# Armament_HUD_Control_Panel.net
KiCad netlist of a schematic drawn in EAGLE
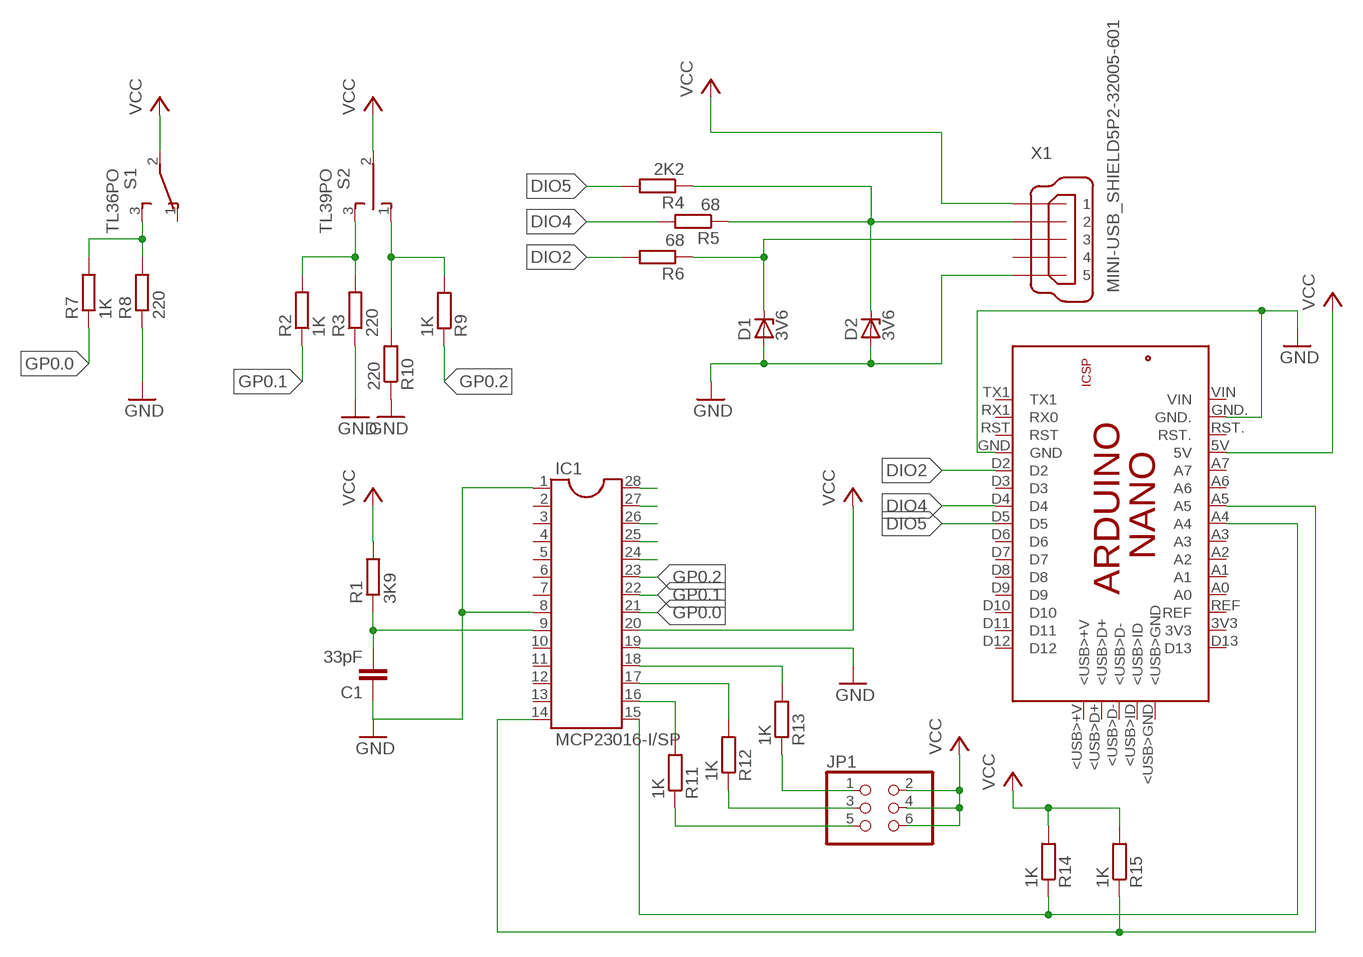
[diagram p0: schematic, sheet 1]

(export (version "E")
  (design (tool "Eeschema 10.0.6"))
  (components
    (comp (ref "C1")
      (value "33pF")
      (footprint "eagle-import:C050-030X075")
      (libsource (lib "eagle-import") (part "C-EU050-030X075"))
    )
    (comp (ref "D1")
      (value "3V6")
      (footprint "eagle-import:DO35Z10")
      (libsource (lib "eagle-import") (part "ZPD"))
    )
    (comp (ref "D2")
      (value "3V6")
      (footprint "eagle-import:DO35Z10")
      (libsource (lib "eagle-import") (part "ZPD"))
    )
    (comp (ref "IC1")
      (value "MCP23016-I/SP")
      (footprint "eagle-import:DIL28-3")
      (libsource (lib "eagle-import") (part "DIL28-3"))
    )
    (comp (ref "JP1")
      (value "PINHD-2X3")
      (footprint "eagle-import:2X03")
      (libsource (lib "eagle-import") (part "PINHD-2X3"))
    )
    (comp (ref "PCB1")
      (value "ARDUINO_NANO")
      (footprint "eagle-import:ARDUINO_NANO")
      (libsource (lib "eagle-import") (part "ARDUINO_NANO"))
    )
    (comp (ref "R1")
      (value "3K9")
      (footprint "eagle-import:0204_7")
      (libsource (lib "eagle-import") (part "R-EU_0204/7"))
    )
    (comp (ref "R2")
      (value "1K")
      (footprint "eagle-import:0204_7")
      (libsource (lib "eagle-import") (part "R-EU_0204/7"))
    )
    (comp (ref "R3")
      (value "220")
      (footprint "eagle-import:0204_7")
      (libsource (lib "eagle-import") (part "R-EU_0204/7"))
    )
    (comp (ref "R4")
      (value "2K2")
      (footprint "eagle-import:0204_7")
      (libsource (lib "eagle-import") (part "R-EU_0204/7"))
    )
    (comp (ref "R5")
      (value "68")
      (footprint "eagle-import:0204_7")
      (libsource (lib "eagle-import") (part "R-EU_0204/7"))
    )
    (comp (ref "R6")
      (value "68")
      (footprint "eagle-import:0204_7")
      (libsource (lib "eagle-import") (part "R-EU_0204/7"))
    )
    (comp (ref "R7")
      (value "1K")
      (footprint "eagle-import:0204_7")
      (libsource (lib "eagle-import") (part "R-EU_0204/7"))
    )
    (comp (ref "R8")
      (value "220")
      (footprint "eagle-import:0204_7")
      (libsource (lib "eagle-import") (part "R-EU_0204/7"))
    )
    (comp (ref "R9")
      (value "1K")
      (footprint "eagle-import:0204_7")
      (libsource (lib "eagle-import") (part "R-EU_0204/7"))
    )
    (comp (ref "R10")
      (value "220")
      (footprint "eagle-import:0204_7")
      (libsource (lib "eagle-import") (part "R-EU_0204/7"))
    )
    (comp (ref "R11")
      (value "1K")
      (footprint "eagle-import:0204_7")
      (libsource (lib "eagle-import") (part "R-EU_0204/7"))
    )
    (comp (ref "R12")
      (value "1K")
      (footprint "eagle-import:0204_7")
      (libsource (lib "eagle-import") (part "R-EU_0204/7"))
    )
    (comp (ref "R13")
      (value "1K")
      (footprint "eagle-import:0204_7")
      (libsource (lib "eagle-import") (part "R-EU_0204/7"))
    )
    (comp (ref "R14")
      (value "1K")
      (footprint "eagle-import:0204_7")
      (libsource (lib "eagle-import") (part "R-EU_0204/7"))
    )
    (comp (ref "R15")
      (value "1K")
      (footprint "eagle-import:0204_7")
      (libsource (lib "eagle-import") (part "R-EU_0204/7"))
    )
    (comp (ref "S1")
      (value "TL36PO")
      (footprint "eagle-import:TL3XPO")
      (libsource (lib "eagle-import") (part "TL36PO"))
    )
    (comp (ref "S2")
      (value "TL39PO")
      (footprint "eagle-import:TL3XPO")
      (libsource (lib "eagle-import") (part "TL39PO"))
    )
    (comp (ref "X1")
      (value "MINI-USB_SHIELD5P2-32005-601")
      (footprint "eagle-import:32005-601")
      (libsource (lib "eagle-import") (part "MINI-USB_SHIELD5P2-32005-601"))
    )
  )
  (nets
    (net (code "1") (name "DIO2") (class "Default")
      (node (ref "PCB1") (pin "D2") (pinfunction "D2_D2") (pintype "bidirectional"))
      (node (ref "R6") (pin "2") (pinfunction "2_2") (pintype "passive"))
    )
    (net (code "2") (name "DIO4") (class "Default")
      (node (ref "PCB1") (pin "D4") (pinfunction "D4_D4") (pintype "bidirectional"))
      (node (ref "R5") (pin "2") (pinfunction "2_2") (pintype "passive"))
    )
    (net (code "3") (name "DIO5") (class "Default")
      (node (ref "PCB1") (pin "D5") (pinfunction "D5_D5") (pintype "bidirectional"))
      (node (ref "R4") (pin "2") (pinfunction "2_2") (pintype "passive"))
    )
    (net (code "4") (name "GND") (class "Default")
      (node (ref "C1") (pin "1") (pinfunction "1_1") (pintype "passive"))
      (node (ref "D1") (pin "A") (pinfunction "A_A") (pintype "passive"))
      (node (ref "D2") (pin "A") (pinfunction "A_A") (pintype "passive"))
      (node (ref "IC1") (pin "1") (pinfunction "1_1") (pintype "passive"))
      (node (ref "IC1") (pin "19") (pinfunction "19_19") (pintype "passive"))
      (node (ref "IC1") (pin "8") (pinfunction "8_8") (pintype "passive"))
      (node (ref "PCB1") (pin "GND") (pinfunction "GND_GND") (pintype "bidirectional"))
      (node (ref "PCB1") (pin "GND.") (pinfunction "GND._GND.") (pintype "bidirectional"))
      (node (ref "R10") (pin "1") (pinfunction "1_1") (pintype "passive"))
      (node (ref "R3") (pin "1") (pinfunction "1_1") (pintype "passive"))
      (node (ref "R8") (pin "1") (pinfunction "1_1") (pintype "passive"))
      (node (ref "X1") (pin "5") (pinfunction "5_5") (pintype "passive"))
    )
    (net (code "5") (name "GP0.0") (class "Default")
      (node (ref "IC1") (pin "21") (pinfunction "21_21") (pintype "passive"))
      (node (ref "R7") (pin "1") (pinfunction "1_1") (pintype "passive"))
    )
    (net (code "6") (name "GP0.1") (class "Default")
      (node (ref "IC1") (pin "22") (pinfunction "22_22") (pintype "passive"))
      (node (ref "R2") (pin "1") (pinfunction "1_1") (pintype "passive"))
    )
    (net (code "7") (name "GP0.2") (class "Default")
      (node (ref "IC1") (pin "23") (pinfunction "23_23") (pintype "passive"))
      (node (ref "R9") (pin "1") (pinfunction "1_1") (pintype "passive"))
    )
    (net (code "8") (name "Net-(C1-Pad2)") (class "Default")
      (node (ref "C1") (pin "2") (pinfunction "2_2") (pintype "passive"))
      (node (ref "IC1") (pin "9") (pinfunction "9_9") (pintype "passive"))
      (node (ref "R1") (pin "1") (pinfunction "1_1") (pintype "passive"))
    )
    (net (code "9") (name "Net-(D1-PadC)") (class "Default")
      (node (ref "D1") (pin "C") (pinfunction "C_C") (pintype "passive"))
      (node (ref "R6") (pin "1") (pinfunction "1_1") (pintype "passive"))
      (node (ref "X1") (pin "3") (pinfunction "3_3") (pintype "passive"))
    )
    (net (code "10") (name "Net-(D2-PadC)") (class "Default")
      (node (ref "D2") (pin "C") (pinfunction "C_C") (pintype "passive"))
      (node (ref "R4") (pin "1") (pinfunction "1_1") (pintype "passive"))
      (node (ref "R5") (pin "1") (pinfunction "1_1") (pintype "passive"))
      (node (ref "X1") (pin "2") (pinfunction "2_2") (pintype "passive"))
    )
    (net (code "11") (name "Net-(IC1-Pad14)") (class "Default")
      (node (ref "IC1") (pin "14") (pinfunction "14_14") (pintype "passive"))
      (node (ref "PCB1") (pin "A5") (pinfunction "A5_A5") (pintype "bidirectional"))
      (node (ref "R15") (pin "1") (pinfunction "1_1") (pintype "passive"))
    )
    (net (code "12") (name "Net-(IC1-Pad15)") (class "Default")
      (node (ref "IC1") (pin "15") (pinfunction "15_15") (pintype "passive"))
      (node (ref "PCB1") (pin "A4") (pinfunction "A4_A4") (pintype "bidirectional"))
      (node (ref "R14") (pin "1") (pinfunction "1_1") (pintype "passive"))
    )
    (net (code "13") (name "Net-(IC1-Pad16)") (class "Default")
      (node (ref "IC1") (pin "16") (pinfunction "16_16") (pintype "passive"))
      (node (ref "R11") (pin "2") (pinfunction "2_2") (pintype "passive"))
    )
    (net (code "14") (name "Net-(IC1-Pad17)") (class "Default")
      (node (ref "IC1") (pin "17") (pinfunction "17_17") (pintype "passive"))
      (node (ref "R12") (pin "2") (pinfunction "2_2") (pintype "passive"))
    )
    (net (code "15") (name "Net-(IC1-Pad18)") (class "Default")
      (node (ref "IC1") (pin "18") (pinfunction "18_18") (pintype "passive"))
      (node (ref "R13") (pin "2") (pinfunction "2_2") (pintype "passive"))
    )
    (net (code "16") (name "Net-(JP1-Pad1)") (class "Default")
      (node (ref "JP1") (pin "1") (pinfunction "1_1") (pintype "passive"))
      (node (ref "R13") (pin "1") (pinfunction "1_1") (pintype "passive"))
    )
    (net (code "17") (name "Net-(JP1-Pad3)") (class "Default")
      (node (ref "JP1") (pin "3") (pinfunction "3_3") (pintype "passive"))
      (node (ref "R12") (pin "1") (pinfunction "1_1") (pintype "passive"))
    )
    (net (code "18") (name "Net-(JP1-Pad5)") (class "Default")
      (node (ref "JP1") (pin "5") (pinfunction "5_5") (pintype "passive"))
      (node (ref "R11") (pin "1") (pinfunction "1_1") (pintype "passive"))
    )
    (net (code "19") (name "Net-(S1-S)") (class "Default")
      (node (ref "R7") (pin "2") (pinfunction "2_2") (pintype "passive"))
      (node (ref "R8") (pin "2") (pinfunction "2_2") (pintype "passive"))
      (node (ref "S1") (pin "3") (pinfunction "S_3") (pintype "passive"))
    )
    (net (code "20") (name "Net-(S2-O)") (class "Default")
      (node (ref "R10") (pin "2") (pinfunction "2_2") (pintype "passive"))
      (node (ref "R9") (pin "2") (pinfunction "2_2") (pintype "passive"))
      (node (ref "S2") (pin "1") (pinfunction "O_1") (pintype "passive"))
    )
    (net (code "21") (name "Net-(S2-S)") (class "Default")
      (node (ref "R2") (pin "2") (pinfunction "2_2") (pintype "passive"))
      (node (ref "R3") (pin "2") (pinfunction "2_2") (pintype "passive"))
      (node (ref "S2") (pin "3") (pinfunction "S_3") (pintype "passive"))
    )
    (net (code "22") (name "VCC") (class "Default")
      (node (ref "IC1") (pin "20") (pinfunction "20_20") (pintype "passive"))
      (node (ref "JP1") (pin "2") (pinfunction "2_2") (pintype "passive"))
      (node (ref "JP1") (pin "4") (pinfunction "4_4") (pintype "passive"))
      (node (ref "JP1") (pin "6") (pinfunction "6_6") (pintype "passive"))
      (node (ref "PCB1") (pin "5V") (pinfunction "5V_5V") (pintype "bidirectional"))
      (node (ref "R1") (pin "2") (pinfunction "2_2") (pintype "passive"))
      (node (ref "R14") (pin "2") (pinfunction "2_2") (pintype "passive"))
      (node (ref "R15") (pin "2") (pinfunction "2_2") (pintype "passive"))
      (node (ref "S1") (pin "2") (pinfunction "P_2") (pintype "passive"))
      (node (ref "S2") (pin "2") (pinfunction "P_2") (pintype "passive"))
      (node (ref "X1") (pin "1") (pinfunction "1_1") (pintype "passive"))
    )
    (net (code "23") (name "unconnected-(IC1-Pad2)") (class "Default")
      (node (ref "IC1") (pin "2") (pinfunction "2_2") (pintype "passive"))
    )
    (net (code "24") (name "unconnected-(IC1-Pad3)") (class "Default")
      (node (ref "IC1") (pin "3") (pinfunction "3_3") (pintype "passive"))
    )
    (net (code "25") (name "unconnected-(IC1-Pad4)") (class "Default")
      (node (ref "IC1") (pin "4") (pinfunction "4_4") (pintype "passive"))
    )
    (net (code "26") (name "unconnected-(IC1-Pad5)") (class "Default")
      (node (ref "IC1") (pin "5") (pinfunction "5_5") (pintype "passive"))
    )
    (net (code "27") (name "unconnected-(IC1-Pad6)") (class "Default")
      (node (ref "IC1") (pin "6") (pinfunction "6_6") (pintype "passive"))
    )
    (net (code "28") (name "unconnected-(IC1-Pad7)") (class "Default")
      (node (ref "IC1") (pin "7") (pinfunction "7_7") (pintype "passive"))
    )
    (net (code "29") (name "unconnected-(IC1-Pad10)") (class "Default")
      (node (ref "IC1") (pin "10") (pinfunction "10_10") (pintype "passive"))
    )
    (net (code "30") (name "unconnected-(IC1-Pad11)") (class "Default")
      (node (ref "IC1") (pin "11") (pinfunction "11_11") (pintype "passive"))
    )
    (net (code "31") (name "unconnected-(IC1-Pad12)") (class "Default")
      (node (ref "IC1") (pin "12") (pinfunction "12_12") (pintype "passive"))
    )
    (net (code "32") (name "unconnected-(IC1-Pad13)") (class "Default")
      (node (ref "IC1") (pin "13") (pinfunction "13_13") (pintype "passive"))
    )
    (net (code "33") (name "unconnected-(IC1-Pad24)") (class "Default")
      (node (ref "IC1") (pin "24") (pinfunction "24_24") (pintype "passive"))
    )
    (net (code "34") (name "unconnected-(IC1-Pad25)") (class "Default")
      (node (ref "IC1") (pin "25") (pinfunction "25_25") (pintype "passive"))
    )
    (net (code "35") (name "unconnected-(IC1-Pad26)") (class "Default")
      (node (ref "IC1") (pin "26") (pinfunction "26_26") (pintype "passive"))
    )
    (net (code "36") (name "unconnected-(IC1-Pad27)") (class "Default")
      (node (ref "IC1") (pin "27") (pinfunction "27_27") (pintype "passive"))
    )
    (net (code "37") (name "unconnected-(IC1-Pad28)") (class "Default")
      (node (ref "IC1") (pin "28") (pinfunction "28_28") (pintype "passive"))
    )
    (net (code "38") (name "unconnected-(PCB1-Pad3V3)") (class "Default")
      (node (ref "PCB1") (pin "3V3") (pinfunction "3V3_3V3") (pintype "bidirectional"))
    )
    (net (code "39") (name "unconnected-(PCB1-Pad5V.)") (class "Default")
      (node (ref "PCB1") (pin "5V.") (pinfunction "5V._5V.") (pintype "bidirectional"))
    )
    (net (code "40") (name "unconnected-(PCB1-Pad<USB>+V)") (class "Default")
      (node (ref "PCB1") (pin "<USB>+V") (pinfunction "<USB>+V_<USB>+V") (pintype "bidirectional"))
    )
    (net (code "41") (name "unconnected-(PCB1-Pad<USB>D+)") (class "Default")
      (node (ref "PCB1") (pin "<USB>D+") (pinfunction "<USB>D+_<USB>D+") (pintype "bidirectional"))
    )
    (net (code "42") (name "unconnected-(PCB1-Pad<USB>D-)") (class "Default")
      (node (ref "PCB1") (pin "<USB>D-") (pinfunction "<USB>D-_<USB>D-") (pintype "bidirectional"))
    )
    (net (code "43") (name "unconnected-(PCB1-Pad<USB>GND)") (class "Default")
      (node (ref "PCB1") (pin "<USB>GND") (pinfunction "<USB>GND_<USB>GND") (pintype "bidirectional"))
    )
    (net (code "44") (name "unconnected-(PCB1-Pad<USB>ID)") (class "Default")
      (node (ref "PCB1") (pin "<USB>ID") (pinfunction "<USB>ID_<USB>ID") (pintype "bidirectional"))
    )
    (net (code "45") (name "unconnected-(PCB1-PadA0)") (class "Default")
      (node (ref "PCB1") (pin "A0") (pinfunction "A0_A0") (pintype "bidirectional"))
    )
    (net (code "46") (name "unconnected-(PCB1-PadA1)") (class "Default")
      (node (ref "PCB1") (pin "A1") (pinfunction "A1_A1") (pintype "bidirectional"))
    )
    (net (code "47") (name "unconnected-(PCB1-PadA2)") (class "Default")
      (node (ref "PCB1") (pin "A2") (pinfunction "A2_A2") (pintype "bidirectional"))
    )
    (net (code "48") (name "unconnected-(PCB1-PadA3)") (class "Default")
      (node (ref "PCB1") (pin "A3") (pinfunction "A3_A3") (pintype "bidirectional"))
    )
    (net (code "49") (name "unconnected-(PCB1-PadA6)") (class "Default")
      (node (ref "PCB1") (pin "A6") (pinfunction "A6_A6") (pintype "bidirectional"))
    )
    (net (code "50") (name "unconnected-(PCB1-PadA7)") (class "Default")
      (node (ref "PCB1") (pin "A7") (pinfunction "A7_A7") (pintype "bidirectional"))
    )
    (net (code "51") (name "unconnected-(PCB1-PadD3)") (class "Default")
      (node (ref "PCB1") (pin "D3") (pinfunction "D3_D3") (pintype "bidirectional"))
    )
    (net (code "52") (name "unconnected-(PCB1-PadD6)") (class "Default")
      (node (ref "PCB1") (pin "D6") (pinfunction "D6_D6") (pintype "bidirectional"))
    )
    (net (code "53") (name "unconnected-(PCB1-PadD7)") (class "Default")
      (node (ref "PCB1") (pin "D7") (pinfunction "D7_D7") (pintype "bidirectional"))
    )
    (net (code "54") (name "unconnected-(PCB1-PadD8)") (class "Default")
      (node (ref "PCB1") (pin "D8") (pinfunction "D8_D8") (pintype "bidirectional"))
    )
    (net (code "55") (name "unconnected-(PCB1-PadD9)") (class "Default")
      (node (ref "PCB1") (pin "D9") (pinfunction "D9_D9") (pintype "bidirectional"))
    )
    (net (code "56") (name "unconnected-(PCB1-PadD10)") (class "Default")
      (node (ref "PCB1") (pin "D10") (pinfunction "D10_D10") (pintype "bidirectional"))
    )
    (net (code "57") (name "unconnected-(PCB1-PadD11)") (class "Default")
      (node (ref "PCB1") (pin "D11") (pinfunction "D11_D11") (pintype "bidirectional"))
    )
    (net (code "58") (name "unconnected-(PCB1-PadD12)") (class "Default")
      (node (ref "PCB1") (pin "D12") (pinfunction "D12_D12") (pintype "bidirectional"))
    )
    (net (code "59") (name "unconnected-(PCB1-PadD13)") (class "Default")
      (node (ref "PCB1") (pin "D13") (pinfunction "D13_D13") (pintype "bidirectional"))
    )
    (net (code "60") (name "unconnected-(PCB1-PadGND_)") (class "Default")
      (node (ref "PCB1") (pin "GND_") (pinfunction "GND__GND_") (pintype "bidirectional"))
    )
    (net (code "61") (name "unconnected-(PCB1-PadMISO)") (class "Default")
      (node (ref "PCB1") (pin "MISO") (pinfunction "MISO_MISO") (pintype "bidirectional"))
    )
    (net (code "62") (name "unconnected-(PCB1-PadMOSI)") (class "Default")
      (node (ref "PCB1") (pin "MOSI") (pinfunction "MOSI_MOSI") (pintype "bidirectional"))
    )
    (net (code "63") (name "unconnected-(PCB1-PadREF)") (class "Default")
      (node (ref "PCB1") (pin "REF") (pinfunction "REF_REF") (pintype "bidirectional"))
    )
    (net (code "64") (name "unconnected-(PCB1-PadRESET..)") (class "Default")
      (node (ref "PCB1") (pin "RESET..") (pinfunction "RESET.._RESET..") (pintype "bidirectional"))
    )
    (net (code "65") (name "unconnected-(PCB1-PadRST)") (class "Default")
      (node (ref "PCB1") (pin "RST") (pinfunction "RST_RST") (pintype "bidirectional"))
    )
    (net (code "66") (name "unconnected-(PCB1-PadRST.)") (class "Default")
      (node (ref "PCB1") (pin "RST.") (pinfunction "RST._RST.") (pintype "bidirectional"))
    )
    (net (code "67") (name "unconnected-(PCB1-PadSCK)") (class "Default")
      (node (ref "PCB1") (pin "SCK") (pinfunction "SCK_SCK") (pintype "bidirectional"))
    )
    (net (code "68") (name "unconnected-(PCB1-PadTX1)") (class "Default")
      (node (ref "PCB1") (pin "TX1") (pinfunction "TX1_TX1") (pintype "bidirectional"))
    )
    (net (code "69") (name "unconnected-(PCB1-PadVIN)") (class "Default")
      (node (ref "PCB1") (pin "VIN") (pinfunction "VIN_VIN") (pintype "bidirectional"))
    )
    (net (code "70") (name "unconnected-(PCB1-RX0-PadRX1)") (class "Default")
      (node (ref "PCB1") (pin "RX1") (pinfunction "RX0_RX1") (pintype "bidirectional"))
    )
    (net (code "71") (name "unconnected-(S1-O-Pad1)") (class "Default")
      (node (ref "S1") (pin "1") (pinfunction "O_1") (pintype "passive"))
    )
    (net (code "72") (name "unconnected-(X1-Pad4)") (class "Default")
      (node (ref "X1") (pin "4") (pinfunction "4_4") (pintype "passive"))
    )
  )
)
